# FM007.net
KiCad netlist of a schematic drawn in Altium Designer
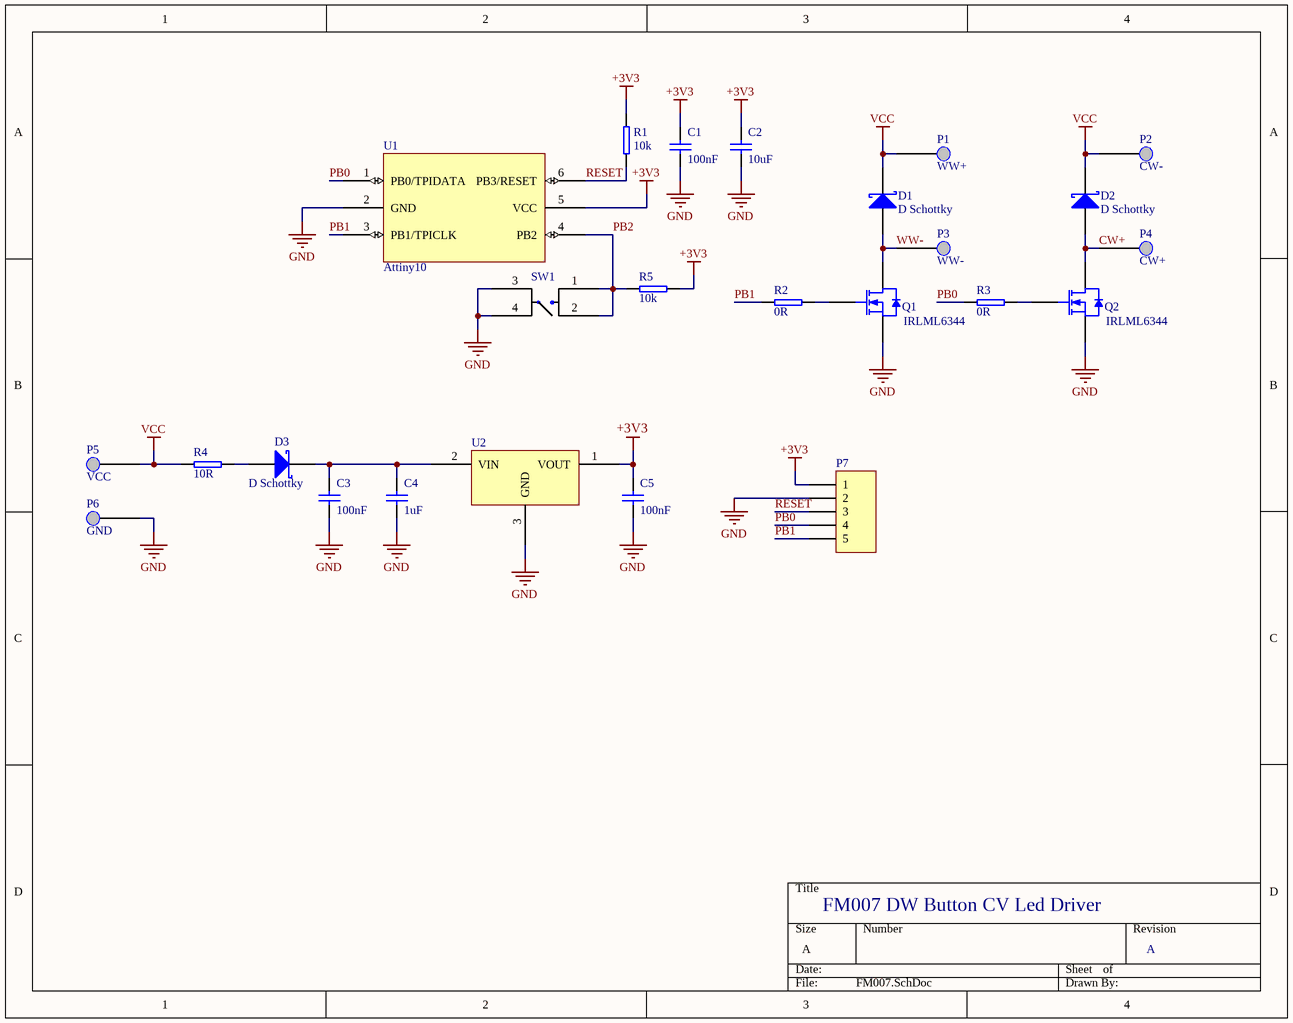
[diagram p0: FM007.SchDoc]

(export (version "E")
  (design (tool "Eeschema 10.0.6"))
  (components
    (comp (ref "C1")
      (value "100nF")
      (footprint "CAP0603L")
      (description "Capacitor (Semiconductor SIM Model)")
      (fields (field (name "PUBLISHER") "Altium Limited"))
      (libsource (lib "Pasywne") (part "C niebiegunowe"))
    )
    (comp (ref "C2")
      (value "10uF")
      (footprint "CAP0805L")
      (description "Capacitor (Semiconductor SIM Model)")
      (fields (field (name "PUBLISHER") "Altium Limited"))
      (libsource (lib "Pasywne") (part "C niebiegunowe"))
    )
    (comp (ref "C3")
      (value "100nF")
      (footprint "CAP0603L")
      (description "Capacitor (Semiconductor SIM Model)")
      (fields (field (name "PUBLISHER") "Altium Limited"))
      (libsource (lib "Pasywne") (part "C niebiegunowe"))
    )
    (comp (ref "C4")
      (value "1uF")
      (footprint "CAP0805L")
      (description "Capacitor (Semiconductor SIM Model)")
      (fields (field (name "PUBLISHER") "Altium Limited"))
      (libsource (lib "Pasywne") (part "C niebiegunowe"))
    )
    (comp (ref "C5")
      (value "100nF")
      (footprint "CAP0603L")
      (description "Capacitor (Semiconductor SIM Model)")
      (fields (field (name "PUBLISHER") "Altium Limited"))
      (libsource (lib "Pasywne") (part "C niebiegunowe"))
    )
    (comp (ref "D1")
      (value "D Schottky")
      (footprint "SOD-323")
      (description "Schottky Diode")
      (fields (field (name "PUBLISHER") "Altium Limited"))
      (libsource (lib "Aktywne") (part "D Schottky"))
    )
    (comp (ref "D2")
      (value "D Schottky")
      (footprint "SOD-323")
      (description "Schottky Diode")
      (fields (field (name "PUBLISHER") "Altium Limited"))
      (libsource (lib "Aktywne") (part "D Schottky"))
    )
    (comp (ref "D3")
      (value "D Schottky")
      (footprint "SOD-323")
      (description "Schottky Diode")
      (fields (field (name "PUBLISHER") "Altium Limited"))
      (libsource (lib "Aktywne") (part "D Schottky"))
    )
    (comp (ref "P1")
      (value "WW+")
      (footprint "Solder PAD SMD 1530")
      (libsource (lib "NO BOM") (part "Solder PAD"))
    )
    (comp (ref "P2")
      (value "CW-")
      (footprint "Solder PAD SMD 1530")
      (libsource (lib "NO BOM") (part "Solder PAD"))
    )
    (comp (ref "P3")
      (value "WW-")
      (footprint "Solder PAD SMD 1530")
      (libsource (lib "NO BOM") (part "Solder PAD"))
    )
    (comp (ref "P4")
      (value "CW+")
      (footprint "Solder PAD SMD 1530")
      (libsource (lib "NO BOM") (part "Solder PAD"))
    )
    (comp (ref "P5")
      (value "VCC")
      (footprint "Solder PAD SMD 1530")
      (libsource (lib "NO BOM") (part "Solder PAD"))
    )
    (comp (ref "P6")
      (value "GND")
      (footprint "Solder PAD SMD 1530")
      (libsource (lib "NO BOM") (part "Solder PAD"))
    )
    (comp (ref "P7")
      (value "~")
      (footprint "5x1.27mm Header")
      (libsource (lib "Konektory i przelaczniki") (part "Header 5"))
    )
    (comp (ref "Q1") (value "IRLML6344") (footprint "SOT23_L") (libsource (lib "Aktywne") (part "MOSFET")))
    (comp (ref "Q2") (value "IRLML6344") (footprint "SOT23_L") (libsource (lib "Aktywne") (part "MOSFET")))
    (comp (ref "R1")
      (value "10k")
      (footprint "RES0603L")
      (description "Semiconductor Resistor")
      (fields (field (name "PUBLISHER") "Altium Limited"))
      (libsource (lib "Pasywne") (part "R"))
    )
    (comp (ref "R2")
      (value "0R")
      (footprint "RES0603L")
      (description "Semiconductor Resistor")
      (fields (field (name "PUBLISHER") "Altium Limited"))
      (libsource (lib "Pasywne") (part "R"))
    )
    (comp (ref "R3")
      (value "0R")
      (footprint "RES0603L")
      (description "Semiconductor Resistor")
      (fields (field (name "PUBLISHER") "Altium Limited"))
      (libsource (lib "Pasywne") (part "R"))
    )
    (comp (ref "R4")
      (value "10R")
      (footprint "RES0603L")
      (description "Semiconductor Resistor")
      (fields (field (name "PUBLISHER") "Altium Limited"))
      (libsource (lib "Pasywne") (part "R"))
    )
    (comp (ref "R5")
      (value "10k")
      (footprint "RES0603L")
      (description "Semiconductor Resistor")
      (fields (field (name "PUBLISHER") "Altium Limited"))
      (libsource (lib "Pasywne") (part "R"))
    )
    (comp (ref "SW1")
      (value "~")
      (footprint "Rafi 1.14.100.503/0000")
      (libsource (lib "Konektory i przelaczniki") (part "Tact Switch"))
    )
    (comp (ref "U1")
      (value "Attiny10")
      (footprint "SOT95P280X100-6N")
      (libsource (lib "Biblioteki_Filip") (part "Attiny10"))
    )
    (comp (ref "U2")
      (value "LM3480/TLV760")
      (footprint "SOT23_L")
      (libsource (lib "Biblioteki_Filip") (part "LM3480/TLV760"))
    )
  )
  (nets
    (net (code "1") (name "+3V3") (class "Default")
      (node (ref "C1") (pin "2") (pinfunction "2_2") (pintype "passive"))
      (node (ref "C2") (pin "2") (pinfunction "2_2") (pintype "passive"))
      (node (ref "C5") (pin "2") (pinfunction "2_2") (pintype "passive"))
      (node (ref "P7") (pin "1") (pinfunction "1_1") (pintype "passive"))
      (node (ref "R1") (pin "1") (pinfunction "1_1") (pintype "passive"))
      (node (ref "R5") (pin "2") (pinfunction "2_2") (pintype "passive"))
      (node (ref "U1") (pin "5") (pinfunction "VCC_5") (pintype "power_in"))
      (node (ref "U2") (pin "1") (pinfunction "VOUT_1") (pintype "power_in"))
    )
    (net (code "2") (name "/CW+") (class "Default")
      (node (ref "D2") (pin "1") (pinfunction "1_1") (pintype "passive"))
      (node (ref "P4") (pin "1") (pinfunction "1_1") (pintype "passive"))
      (node (ref "Q2") (pin "3") (pinfunction "D_3") (pintype "passive"))
    )
    (net (code "3") (name "/PB0") (class "Default")
      (node (ref "P7") (pin "4") (pinfunction "4_4") (pintype "passive"))
      (node (ref "R3") (pin "1") (pinfunction "1_1") (pintype "passive"))
      (node (ref "U1") (pin "1") (pinfunction "PB0/TPIDATA_1") (pintype "bidirectional"))
    )
    (net (code "4") (name "/PB1") (class "Default")
      (node (ref "P7") (pin "5") (pinfunction "5_5") (pintype "passive"))
      (node (ref "R2") (pin "1") (pinfunction "1_1") (pintype "passive"))
      (node (ref "U1") (pin "3") (pinfunction "PB1/TPICLK_3") (pintype "bidirectional"))
    )
    (net (code "5") (name "/PB2") (class "Default")
      (node (ref "R5") (pin "1") (pinfunction "1_1") (pintype "passive"))
      (node (ref "SW1") (pin "1") (pinfunction "1_1") (pintype "passive"))
      (node (ref "SW1") (pin "2") (pinfunction "2_2") (pintype "passive"))
      (node (ref "U1") (pin "4") (pinfunction "PB2_4") (pintype "bidirectional"))
    )
    (net (code "6") (name "/RESET") (class "Default")
      (node (ref "P7") (pin "3") (pinfunction "3_3") (pintype "passive"))
      (node (ref "R1") (pin "2") (pinfunction "2_2") (pintype "passive"))
      (node (ref "U1") (pin "6") (pinfunction "PB3/RESET_6") (pintype "bidirectional"))
    )
    (net (code "7") (name "/WW-") (class "Default")
      (node (ref "D1") (pin "1") (pinfunction "1_1") (pintype "passive"))
      (node (ref "P3") (pin "1") (pinfunction "1_1") (pintype "passive"))
      (node (ref "Q1") (pin "3") (pinfunction "D_3") (pintype "passive"))
    )
    (net (code "8") (name "GND") (class "Default")
      (node (ref "C1") (pin "1") (pinfunction "1_1") (pintype "passive"))
      (node (ref "C2") (pin "1") (pinfunction "1_1") (pintype "passive"))
      (node (ref "C3") (pin "1") (pinfunction "1_1") (pintype "passive"))
      (node (ref "C4") (pin "1") (pinfunction "1_1") (pintype "passive"))
      (node (ref "C5") (pin "1") (pinfunction "1_1") (pintype "passive"))
      (node (ref "P6") (pin "1") (pinfunction "1_1") (pintype "passive"))
      (node (ref "P7") (pin "2") (pinfunction "2_2") (pintype "passive"))
      (node (ref "Q1") (pin "2") (pinfunction "S_2") (pintype "passive"))
      (node (ref "Q2") (pin "2") (pinfunction "S_2") (pintype "passive"))
      (node (ref "SW1") (pin "3") (pinfunction "3_3") (pintype "passive"))
      (node (ref "SW1") (pin "4") (pinfunction "4_4") (pintype "passive"))
      (node (ref "U1") (pin "2") (pinfunction "GND_2") (pintype "power_in"))
      (node (ref "U2") (pin "3") (pinfunction "GND_3") (pintype "power_in"))
    )
    (net (code "9") (name "Net-(D3-Pad1)") (class "Default")
      (node (ref "D3") (pin "1") (pinfunction "1_1") (pintype "passive"))
      (node (ref "R4") (pin "2") (pinfunction "2_2") (pintype "passive"))
    )
    (net (code "10") (name "Net-(Q1-G)") (class "Default")
      (node (ref "Q1") (pin "1") (pinfunction "G_1") (pintype "passive"))
      (node (ref "R2") (pin "2") (pinfunction "2_2") (pintype "passive"))
    )
    (net (code "11") (name "Net-(Q2-G)") (class "Default")
      (node (ref "Q2") (pin "1") (pinfunction "G_1") (pintype "passive"))
      (node (ref "R3") (pin "2") (pinfunction "2_2") (pintype "passive"))
    )
    (net (code "12") (name "Net-(U2-VIN)") (class "Default")
      (node (ref "C3") (pin "2") (pinfunction "2_2") (pintype "passive"))
      (node (ref "C4") (pin "2") (pinfunction "2_2") (pintype "passive"))
      (node (ref "D3") (pin "2") (pinfunction "2_2") (pintype "passive"))
      (node (ref "U2") (pin "2") (pinfunction "VIN_2") (pintype "power_in"))
    )
    (net (code "13") (name "VCC") (class "Default")
      (node (ref "D1") (pin "2") (pinfunction "2_2") (pintype "passive"))
      (node (ref "D2") (pin "2") (pinfunction "2_2") (pintype "passive"))
      (node (ref "P1") (pin "1") (pinfunction "1_1") (pintype "passive"))
      (node (ref "P2") (pin "1") (pinfunction "1_1") (pintype "passive"))
      (node (ref "P5") (pin "1") (pinfunction "1_1") (pintype "passive"))
      (node (ref "R4") (pin "1") (pinfunction "1_1") (pintype "passive"))
    )
  )
)
